# WiFiDMX4Channel.net
KiCad netlist of a schematic drawn in EAGLE
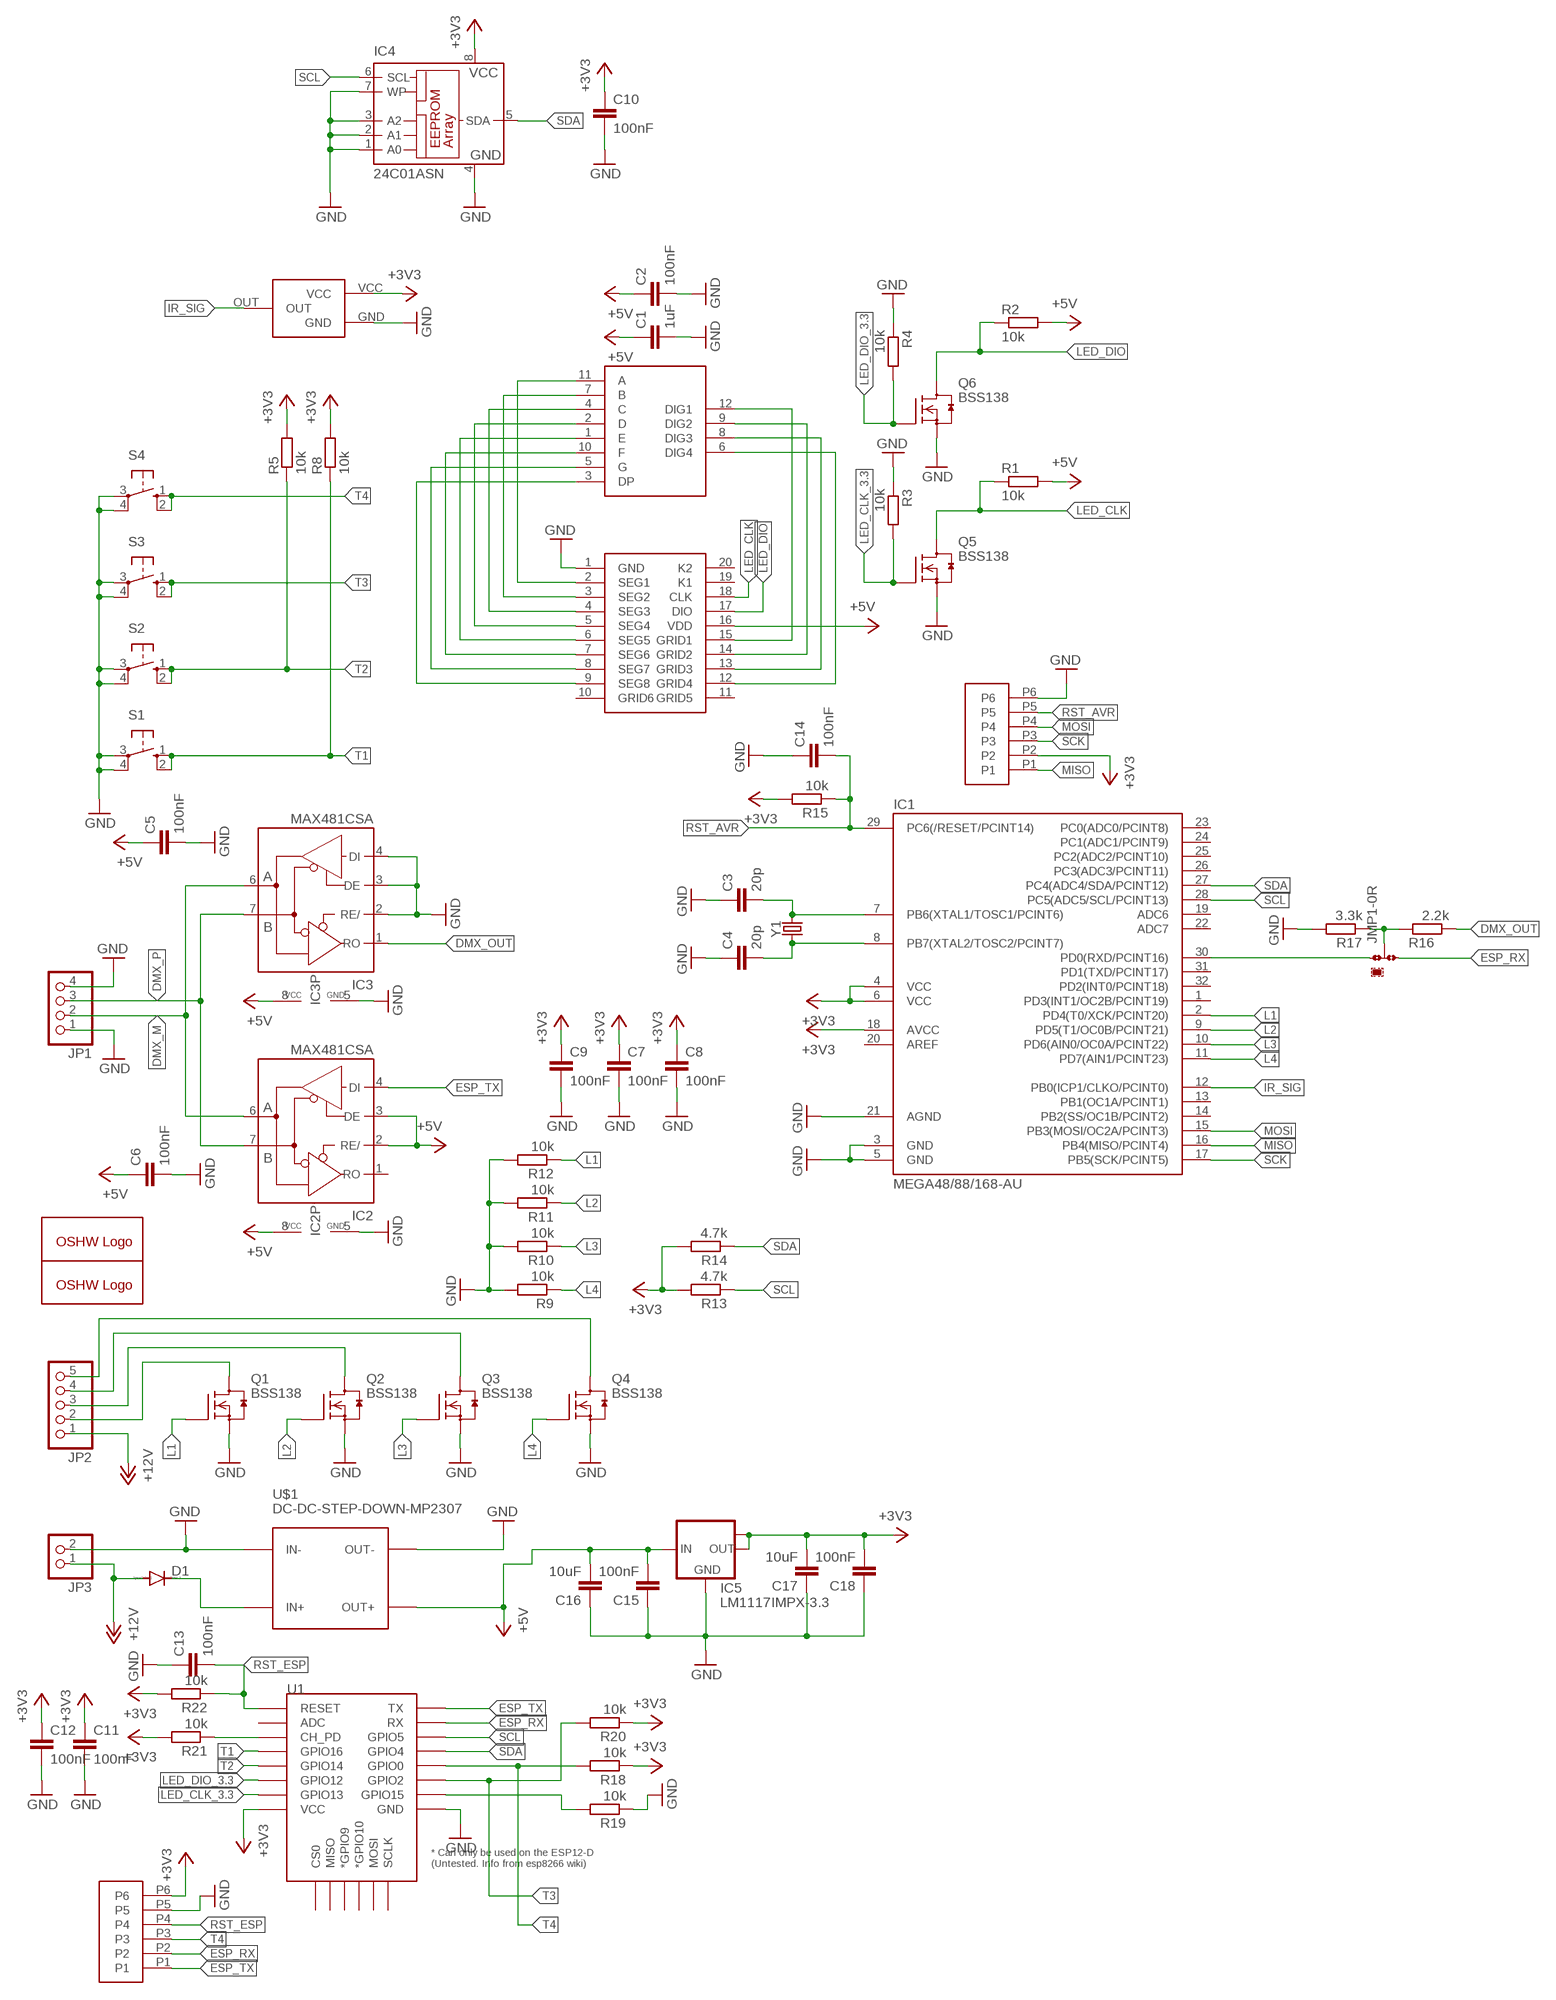
[diagram p0: schematic, sheet 1]

(export (version "E")
  (design (tool "Eeschema 10.0.6"))
  (components
    (comp (ref "C1")
      (value "1uF")
      (footprint "eagle-import:C0603")
      (libsource (lib "eagle-import") (part "C-EUC0603"))
    )
    (comp (ref "C2")
      (value "100nF")
      (footprint "eagle-import:C0603")
      (libsource (lib "eagle-import") (part "C-EUC0603"))
    )
    (comp (ref "C3")
      (value "20p")
      (footprint "eagle-import:C0603")
      (libsource (lib "eagle-import") (part "C-EUC0603"))
    )
    (comp (ref "C4")
      (value "20p")
      (footprint "eagle-import:C0603")
      (libsource (lib "eagle-import") (part "C-EUC0603"))
    )
    (comp (ref "C5")
      (value "100nF")
      (footprint "eagle-import:C0603")
      (libsource (lib "eagle-import") (part "C-EUC0603"))
    )
    (comp (ref "C6")
      (value "100nF")
      (footprint "eagle-import:C0603")
      (libsource (lib "eagle-import") (part "C-EUC0603"))
    )
    (comp (ref "C7")
      (value "100nF")
      (footprint "eagle-import:C0603")
      (libsource (lib "eagle-import") (part "C-EUC0603"))
    )
    (comp (ref "C8")
      (value "100nF")
      (footprint "eagle-import:C0603")
      (libsource (lib "eagle-import") (part "C-EUC0603"))
    )
    (comp (ref "C9")
      (value "100nF")
      (footprint "eagle-import:C0603")
      (libsource (lib "eagle-import") (part "C-EUC0603"))
    )
    (comp (ref "C10")
      (value "100nF")
      (footprint "eagle-import:C0603")
      (libsource (lib "eagle-import") (part "C-EUC0603"))
    )
    (comp (ref "C11")
      (value "100nF")
      (footprint "eagle-import:C0603")
      (libsource (lib "eagle-import") (part "C-EUC0603"))
    )
    (comp (ref "C12")
      (value "100nF")
      (footprint "eagle-import:C0603")
      (libsource (lib "eagle-import") (part "C-EUC0603"))
    )
    (comp (ref "C13")
      (value "100nF")
      (footprint "eagle-import:C0603")
      (libsource (lib "eagle-import") (part "C-EUC0603"))
    )
    (comp (ref "C14")
      (value "100nF")
      (footprint "eagle-import:C0603")
      (libsource (lib "eagle-import") (part "C-EUC0603"))
    )
    (comp (ref "C15")
      (value "100nF")
      (footprint "eagle-import:C0603")
      (libsource (lib "eagle-import") (part "C-EUC0603"))
    )
    (comp (ref "C16")
      (value "10uF")
      (footprint "eagle-import:C0603")
      (libsource (lib "eagle-import") (part "C-EUC0603"))
    )
    (comp (ref "C17")
      (value "10uF")
      (footprint "eagle-import:C0603")
      (libsource (lib "eagle-import") (part "C-EUC0603"))
    )
    (comp (ref "C18")
      (value "100nF")
      (footprint "eagle-import:C0603")
      (libsource (lib "eagle-import") (part "C-EUC0603"))
    )
    (comp (ref "D1")
      (value "DIODE-DO214AC")
      (footprint "eagle-import:DO214AC")
      (libsource (lib "eagle-import") (part "DIODE-DO214AC"))
    )
    (comp (ref "GOLD_ORB_SM1")
      (value "OSHWLOGOLOGO5MM")
      (footprint "eagle-import:OSHW_5MM")
      (libsource (lib "eagle-import") (part "OSHWLOGOLOGO5MM"))
    )
    (comp (ref "GOLD_ORB_SM2")
      (value "OSHWLOGOLOGO5MM")
      (footprint "eagle-import:OSHW_5MM")
      (libsource (lib "eagle-import") (part "OSHWLOGOLOGO5MM"))
    )
    (comp (ref "IC1")
      (value "MEGA48/88/168-AU")
      (footprint "eagle-import:TQFP32-08")
      (libsource (lib "eagle-import") (part "MEGA48/88/168-AU"))
    )
    (comp (ref "IC2")
      (value "MAX481CSA")
      (footprint "eagle-import:SO08")
      (libsource (lib "eagle-import") (part "MAX481CSA"))
    )
    (comp (ref "IC3")
      (value "MAX481CSA")
      (footprint "eagle-import:SO08")
      (libsource (lib "eagle-import") (part "MAX481CSA"))
    )
    (comp (ref "IC4")
      (value "24C01ASN")
      (footprint "eagle-import:SO-08")
      (fields (field (name "MPN") "AT24C01BN-SH-B"))
      (libsource (lib "eagle-import") (part "24CSN01A"))
    )
    (comp (ref "IC5")
      (value "LM1117IMPX-3.3")
      (footprint "eagle-import:SOT223")
      (libsource (lib "eagle-import") (part "LM1117IMPX-3.3"))
    )
    (comp (ref "JMP1")
      (value "0R-JUMPA")
      (footprint "eagle-import:A0R-JMP")
      (libsource (lib "eagle-import") (part "0R-JUMPA"))
    )
    (comp (ref "JP1")
      (value "PINHD-1X4_2.54")
      (footprint "eagle-import:1X04")
      (libsource (lib "eagle-import") (part "PINHD-1X4_2.54"))
    )
    (comp (ref "JP2")
      (value "PINHD-1X5_2.54")
      (footprint "eagle-import:1X05")
      (libsource (lib "eagle-import") (part "PINHD-1X5_2.54"))
    )
    (comp (ref "JP3")
      (value "PINHD-1X2_2.54")
      (footprint "eagle-import:1X02")
      (libsource (lib "eagle-import") (part "PINHD-1X2_2.54"))
    )
    (comp (ref "Q1")
      (value "BSS138")
      (footprint "eagle-import:SOT23")
      (libsource (lib "eagle-import") (part "BSS138"))
    )
    (comp (ref "Q2")
      (value "BSS138")
      (footprint "eagle-import:SOT23")
      (libsource (lib "eagle-import") (part "BSS138"))
    )
    (comp (ref "Q3")
      (value "BSS138")
      (footprint "eagle-import:SOT23")
      (libsource (lib "eagle-import") (part "BSS138"))
    )
    (comp (ref "Q4")
      (value "BSS138")
      (footprint "eagle-import:SOT23")
      (libsource (lib "eagle-import") (part "BSS138"))
    )
    (comp (ref "Q5")
      (value "BSS138")
      (footprint "eagle-import:SOT23")
      (libsource (lib "eagle-import") (part "BSS138"))
    )
    (comp (ref "Q6")
      (value "BSS138")
      (footprint "eagle-import:SOT23")
      (libsource (lib "eagle-import") (part "BSS138"))
    )
    (comp (ref "R1")
      (value "10k")
      (footprint "eagle-import:R0603")
      (libsource (lib "eagle-import") (part "R-EU_R0603"))
    )
    (comp (ref "R2")
      (value "10k")
      (footprint "eagle-import:R0603")
      (libsource (lib "eagle-import") (part "R-EU_R0603"))
    )
    (comp (ref "R3")
      (value "10k")
      (footprint "eagle-import:R0603")
      (libsource (lib "eagle-import") (part "R-EU_R0603"))
    )
    (comp (ref "R4")
      (value "10k")
      (footprint "eagle-import:R0603")
      (libsource (lib "eagle-import") (part "R-EU_R0603"))
    )
    (comp (ref "R5")
      (value "10k")
      (footprint "eagle-import:R0603")
      (libsource (lib "eagle-import") (part "R-EU_R0603"))
    )
    (comp (ref "R8")
      (value "10k")
      (footprint "eagle-import:R0603")
      (libsource (lib "eagle-import") (part "R-EU_R0603"))
    )
    (comp (ref "R9")
      (value "10k")
      (footprint "eagle-import:R0603")
      (libsource (lib "eagle-import") (part "R-EU_R0603"))
    )
    (comp (ref "R10")
      (value "10k")
      (footprint "eagle-import:R0603")
      (libsource (lib "eagle-import") (part "R-EU_R0603"))
    )
    (comp (ref "R11")
      (value "10k")
      (footprint "eagle-import:R0603")
      (libsource (lib "eagle-import") (part "R-EU_R0603"))
    )
    (comp (ref "R12")
      (value "10k")
      (footprint "eagle-import:R0603")
      (libsource (lib "eagle-import") (part "R-EU_R0603"))
    )
    (comp (ref "R13")
      (value "4.7k")
      (footprint "eagle-import:R0603")
      (libsource (lib "eagle-import") (part "R-EU_R0603"))
    )
    (comp (ref "R14")
      (value "4.7k")
      (footprint "eagle-import:R0603")
      (libsource (lib "eagle-import") (part "R-EU_R0603"))
    )
    (comp (ref "R15")
      (value "10k")
      (footprint "eagle-import:R0603")
      (libsource (lib "eagle-import") (part "R-EU_R0603"))
    )
    (comp (ref "R16")
      (value "2.2k")
      (footprint "eagle-import:R0603")
      (libsource (lib "eagle-import") (part "R-EU_R0603"))
    )
    (comp (ref "R17")
      (value "3.3k")
      (footprint "eagle-import:R0603")
      (libsource (lib "eagle-import") (part "R-EU_R0603"))
    )
    (comp (ref "R18")
      (value "10k")
      (footprint "eagle-import:R0603")
      (libsource (lib "eagle-import") (part "R-EU_R0603"))
    )
    (comp (ref "R19")
      (value "10k")
      (footprint "eagle-import:R0603")
      (libsource (lib "eagle-import") (part "R-EU_R0603"))
    )
    (comp (ref "R20")
      (value "10k")
      (footprint "eagle-import:R0603")
      (libsource (lib "eagle-import") (part "R-EU_R0603"))
    )
    (comp (ref "R21")
      (value "10k")
      (footprint "eagle-import:R0603")
      (libsource (lib "eagle-import") (part "R-EU_R0603"))
    )
    (comp (ref "R22")
      (value "10k")
      (footprint "eagle-import:R0603")
      (libsource (lib "eagle-import") (part "R-EU_R0603"))
    )
    (comp (ref "S1")
      (value "10-XX")
      (footprint "eagle-import:B3F-10XX")
      (fields (field (name "MPN") "B3F-1000"))
      (libsource (lib "eagle-import") (part "10-XX"))
    )
    (comp (ref "S2")
      (value "10-XX")
      (footprint "eagle-import:B3F-10XX")
      (fields (field (name "MPN") "B3F-1000"))
      (libsource (lib "eagle-import") (part "10-XX"))
    )
    (comp (ref "S3")
      (value "10-XX")
      (footprint "eagle-import:B3F-10XX")
      (fields (field (name "MPN") "B3F-1000"))
      (libsource (lib "eagle-import") (part "10-XX"))
    )
    (comp (ref "S4")
      (value "10-XX")
      (footprint "eagle-import:B3F-10XX")
      (fields (field (name "MPN") "B3F-1000"))
      (libsource (lib "eagle-import") (part "10-XX"))
    )
    (comp (ref "U$1")
      (value "DC-DC-STEP-DOWN-MP2307")
      (footprint "eagle-import:DC-DC-STEP-DOWN-MP2307")
      (libsource (lib "eagle-import") (part "DC-DC-STEP-DOWN-MP2307"))
    )
    (comp (ref "U$2")
      (value "4-DIGIT-7-SEGMENT")
      (footprint "eagle-import:7SETG-1")
      (libsource (lib "eagle-import") (part "4-DIGIT-7-SEGMENT"))
    )
    (comp (ref "U$3")
      (value "TM1637-SOP20")
      (footprint "eagle-import:SO20W")
      (libsource (lib "eagle-import") (part "TM1637-SOP20"))
    )
    (comp (ref "U$4")
      (value "PC838")
      (footprint "eagle-import:PC838")
      (libsource (lib "eagle-import") (part "PC838"))
    )
    (comp (ref "U$5")
      (value "6P-1.27")
      (footprint "eagle-import:6P-1.27")
      (libsource (lib "eagle-import") (part "6P-1.27"))
    )
    (comp (ref "U$6")
      (value "6P-1.27")
      (footprint "eagle-import:6P-1.27")
      (libsource (lib "eagle-import") (part "6P-1.27"))
    )
    (comp (ref "U1")
      (value "ESP12ESMD")
      (footprint "eagle-import:ESP12E-SMD")
      (libsource (lib "eagle-import") (part "ESP12ESMD"))
    )
    (comp (ref "Y1")
      (value "CRYSTALSMD-5X3.2-2PAD")
      (footprint "eagle-import:CRYSTAL-SMD-5X3.2-2PAD")
      (libsource (lib "eagle-import") (part "CRYSTALSMD-5X3.2-2PAD"))
    )
  )
  (nets
    (net (code "1") (name "+3V3") (class "Default")
      (node (ref "C10") (pin "1") (pinfunction "1_1") (pintype "passive"))
      (node (ref "C11") (pin "1") (pinfunction "1_1") (pintype "passive"))
      (node (ref "C12") (pin "1") (pinfunction "1_1") (pintype "passive"))
      (node (ref "C17") (pin "2") (pinfunction "2_2") (pintype "passive"))
      (node (ref "C18") (pin "2") (pinfunction "2_2") (pintype "passive"))
      (node (ref "C7") (pin "1") (pinfunction "1_1") (pintype "passive"))
      (node (ref "C8") (pin "1") (pinfunction "1_1") (pintype "passive"))
      (node (ref "C9") (pin "1") (pinfunction "1_1") (pintype "passive"))
      (node (ref "IC1") (pin "18") (pinfunction "AVCC_18") (pintype "passive"))
      (node (ref "IC1") (pin "4") (pinfunction "VCC_4") (pintype "power_in"))
      (node (ref "IC1") (pin "6") (pinfunction "VCC_6") (pintype "power_in"))
      (node (ref "IC4") (pin "8") (pinfunction "VCC_8") (pintype "power_in"))
      (node (ref "IC5") (pin "2") (pinfunction "OUT_2") (pintype "passive"))
      (node (ref "IC5") (pin "TAB") (pinfunction "OUT1_TAB") (pintype "passive"))
      (node (ref "R13") (pin "2") (pinfunction "2_2") (pintype "passive"))
      (node (ref "R14") (pin "2") (pinfunction "2_2") (pintype "passive"))
      (node (ref "R15") (pin "2") (pinfunction "2_2") (pintype "passive"))
      (node (ref "R18") (pin "1") (pinfunction "1_1") (pintype "passive"))
      (node (ref "R20") (pin "1") (pinfunction "1_1") (pintype "passive"))
      (node (ref "R21") (pin "2") (pinfunction "2_2") (pintype "passive"))
      (node (ref "R22") (pin "2") (pinfunction "2_2") (pintype "passive"))
      (node (ref "R5") (pin "2") (pinfunction "2_2") (pintype "passive"))
      (node (ref "R8") (pin "2") (pinfunction "2_2") (pintype "passive"))
      (node (ref "U$4") (pin "VCC") (pinfunction "VCC_VCC") (pintype "bidirectional"))
      (node (ref "U$5") (pin "P6") (pinfunction "P6_P6") (pintype "bidirectional"))
      (node (ref "U$6") (pin "P2") (pinfunction "P2_P2") (pintype "bidirectional"))
      (node (ref "U1") (pin "VCC") (pinfunction "VCC_VCC") (pintype "bidirectional"))
    )
    (net (code "2") (name "+5V") (class "Default")
      (node (ref "C1") (pin "1") (pinfunction "1_1") (pintype "passive"))
      (node (ref "C15") (pin "2") (pinfunction "2_2") (pintype "passive"))
      (node (ref "C16") (pin "2") (pinfunction "2_2") (pintype "passive"))
      (node (ref "C2") (pin "1") (pinfunction "1_1") (pintype "passive"))
      (node (ref "C5") (pin "1") (pinfunction "1_1") (pintype "passive"))
      (node (ref "C6") (pin "1") (pinfunction "1_1") (pintype "passive"))
      (node (ref "IC2") (pin "2") (pinfunction "RE/_2") (pintype "input"))
      (node (ref "IC2") (pin "3") (pinfunction "DE_3") (pintype "input"))
      (node (ref "IC2") (pin "8") (pinfunction "VCC_8") (pintype "power_in"))
      (node (ref "IC3") (pin "8") (pinfunction "VCC_8") (pintype "power_in"))
      (node (ref "IC5") (pin "3") (pinfunction "IN_3") (pintype "input"))
      (node (ref "R1") (pin "2") (pinfunction "2_2") (pintype "passive"))
      (node (ref "R2") (pin "2") (pinfunction "2_2") (pintype "passive"))
      (node (ref "U$1") (pin "OUT+") (pinfunction "OUT+_OUT+") (pintype "bidirectional"))
      (node (ref "U$3") (pin "16") (pinfunction "VDD_16") (pintype "bidirectional"))
    )
    (net (code "3") (name "+12V") (class "Default")
      (node (ref "D1") (pin "A") (pinfunction "A_A") (pintype "passive"))
      (node (ref "JP2") (pin "1") (pinfunction "1_1") (pintype "passive"))
      (node (ref "JP3") (pin "1") (pinfunction "1_1") (pintype "passive"))
    )
    (net (code "4") (name "DMX_M") (class "Default")
      (node (ref "IC2") (pin "6") (pinfunction "A_6") (pintype "passive"))
      (node (ref "IC3") (pin "6") (pinfunction "A_6") (pintype "passive"))
      (node (ref "JP1") (pin "2") (pinfunction "2_2") (pintype "passive"))
    )
    (net (code "5") (name "DMX_OUT") (class "Default")
      (node (ref "IC3") (pin "1") (pinfunction "RO_1") (pintype "output"))
      (node (ref "R16") (pin "1") (pinfunction "1_1") (pintype "passive"))
    )
    (net (code "6") (name "DMX_P") (class "Default")
      (node (ref "IC2") (pin "7") (pinfunction "B_7") (pintype "passive"))
      (node (ref "IC3") (pin "7") (pinfunction "B_7") (pintype "passive"))
      (node (ref "JP1") (pin "3") (pinfunction "3_3") (pintype "passive"))
    )
    (net (code "7") (name "ESP_RX") (class "Default")
      (node (ref "JMP1") (pin "3") (pinfunction "3_3") (pintype "passive"))
      (node (ref "U$5") (pin "P2") (pinfunction "P2_P2") (pintype "bidirectional"))
      (node (ref "U1") (pin "RXD0") (pinfunction "RX_RXD0") (pintype "bidirectional"))
    )
    (net (code "8") (name "ESP_TX") (class "Default")
      (node (ref "IC2") (pin "4") (pinfunction "DI_4") (pintype "input"))
      (node (ref "U$5") (pin "P1") (pinfunction "P1_P1") (pintype "bidirectional"))
      (node (ref "U1") (pin "TXD0") (pinfunction "TX_TXD0") (pintype "bidirectional"))
    )
    (net (code "9") (name "GND") (class "Default")
      (node (ref "C1") (pin "2") (pinfunction "2_2") (pintype "passive"))
      (node (ref "C10") (pin "2") (pinfunction "2_2") (pintype "passive"))
      (node (ref "C11") (pin "2") (pinfunction "2_2") (pintype "passive"))
      (node (ref "C12") (pin "2") (pinfunction "2_2") (pintype "passive"))
      (node (ref "C13") (pin "1") (pinfunction "1_1") (pintype "passive"))
      (node (ref "C14") (pin "1") (pinfunction "1_1") (pintype "passive"))
      (node (ref "C15") (pin "1") (pinfunction "1_1") (pintype "passive"))
      (node (ref "C16") (pin "1") (pinfunction "1_1") (pintype "passive"))
      (node (ref "C17") (pin "1") (pinfunction "1_1") (pintype "passive"))
      (node (ref "C18") (pin "1") (pinfunction "1_1") (pintype "passive"))
      (node (ref "C2") (pin "2") (pinfunction "2_2") (pintype "passive"))
      (node (ref "C3") (pin "1") (pinfunction "1_1") (pintype "passive"))
      (node (ref "C4") (pin "1") (pinfunction "1_1") (pintype "passive"))
      (node (ref "C5") (pin "2") (pinfunction "2_2") (pintype "passive"))
      (node (ref "C6") (pin "2") (pinfunction "2_2") (pintype "passive"))
      (node (ref "C7") (pin "2") (pinfunction "2_2") (pintype "passive"))
      (node (ref "C8") (pin "2") (pinfunction "2_2") (pintype "passive"))
      (node (ref "C9") (pin "2") (pinfunction "2_2") (pintype "passive"))
      (node (ref "IC1") (pin "21") (pinfunction "AGND_21") (pintype "power_in"))
      (node (ref "IC1") (pin "3") (pinfunction "GND_3") (pintype "power_in"))
      (node (ref "IC1") (pin "5") (pinfunction "GND_5") (pintype "power_in"))
      (node (ref "IC2") (pin "5") (pinfunction "GND_5") (pintype "power_in"))
      (node (ref "IC3") (pin "2") (pinfunction "RE/_2") (pintype "input"))
      (node (ref "IC3") (pin "3") (pinfunction "DE_3") (pintype "input"))
      (node (ref "IC3") (pin "4") (pinfunction "DI_4") (pintype "input"))
      (node (ref "IC3") (pin "5") (pinfunction "GND_5") (pintype "power_in"))
      (node (ref "IC4") (pin "1") (pinfunction "A0_1") (pintype "input"))
      (node (ref "IC4") (pin "2") (pinfunction "A1_2") (pintype "input"))
      (node (ref "IC4") (pin "3") (pinfunction "A2_3") (pintype "input"))
      (node (ref "IC4") (pin "4") (pinfunction "GND_4") (pintype "power_in"))
      (node (ref "IC4") (pin "7") (pinfunction "WP_7") (pintype "input"))
      (node (ref "IC5") (pin "1") (pinfunction "GND_1") (pintype "input"))
      (node (ref "JP1") (pin "1") (pinfunction "1_1") (pintype "passive"))
      (node (ref "JP1") (pin "4") (pinfunction "4_4") (pintype "passive"))
      (node (ref "JP3") (pin "2") (pinfunction "2_2") (pintype "passive"))
      (node (ref "Q1") (pin "2") (pinfunction "S_2") (pintype "passive"))
      (node (ref "Q2") (pin "2") (pinfunction "S_2") (pintype "passive"))
      (node (ref "Q3") (pin "2") (pinfunction "S_2") (pintype "passive"))
      (node (ref "Q4") (pin "2") (pinfunction "S_2") (pintype "passive"))
      (node (ref "Q5") (pin "2") (pinfunction "S_2") (pintype "passive"))
      (node (ref "Q6") (pin "2") (pinfunction "S_2") (pintype "passive"))
      (node (ref "R10") (pin "2") (pinfunction "2_2") (pintype "passive"))
      (node (ref "R11") (pin "2") (pinfunction "2_2") (pintype "passive"))
      (node (ref "R12") (pin "2") (pinfunction "2_2") (pintype "passive"))
      (node (ref "R17") (pin "2") (pinfunction "2_2") (pintype "passive"))
      (node (ref "R19") (pin "1") (pinfunction "1_1") (pintype "passive"))
      (node (ref "R3") (pin "1") (pinfunction "1_1") (pintype "passive"))
      (node (ref "R4") (pin "1") (pinfunction "1_1") (pintype "passive"))
      (node (ref "R9") (pin "2") (pinfunction "2_2") (pintype "passive"))
      (node (ref "S1") (pin "3") (pinfunction "P_3") (pintype "passive"))
      (node (ref "S1") (pin "4") (pinfunction "P1_4") (pintype "passive"))
      (node (ref "S2") (pin "3") (pinfunction "P_3") (pintype "passive"))
      (node (ref "S2") (pin "4") (pinfunction "P1_4") (pintype "passive"))
      (node (ref "S3") (pin "3") (pinfunction "P_3") (pintype "passive"))
      (node (ref "S3") (pin "4") (pinfunction "P1_4") (pintype "passive"))
      (node (ref "S4") (pin "3") (pinfunction "P_3") (pintype "passive"))
      (node (ref "S4") (pin "4") (pinfunction "P1_4") (pintype "passive"))
      (node (ref "U$1") (pin "IN-") (pinfunction "IN-_IN-") (pintype "bidirectional"))
      (node (ref "U$1") (pin "OUT-") (pinfunction "OUT-_OUT-") (pintype "bidirectional"))
      (node (ref "U$3") (pin "1") (pinfunction "GND_1") (pintype "bidirectional"))
      (node (ref "U$4") (pin "GND") (pinfunction "GND_GND") (pintype "bidirectional"))
      (node (ref "U$5") (pin "P5") (pinfunction "P5_P5") (pintype "bidirectional"))
      (node (ref "U$6") (pin "P6") (pinfunction "P6_P6") (pintype "bidirectional"))
      (node (ref "U1") (pin "GND") (pinfunction "GND_GND") (pintype "bidirectional"))
    )
    (net (code "10") (name "IR_SIG") (class "Default")
      (node (ref "IC1") (pin "12") (pinfunction "PB0(ICP1/CLKO/PCINT0)_12") (pintype "bidirectional"))
      (node (ref "U$4") (pin "OUT") (pinfunction "OUT_OUT") (pintype "bidirectional"))
    )
    (net (code "11") (name "L1") (class "Default")
      (node (ref "IC1") (pin "2") (pinfunction "PD4(T0/XCK/PCINT20)_2") (pintype "bidirectional"))
      (node (ref "Q1") (pin "1") (pinfunction "G_1") (pintype "passive"))
      (node (ref "R12") (pin "1") (pinfunction "1_1") (pintype "passive"))
    )
    (net (code "12") (name "L2") (class "Default")
      (node (ref "IC1") (pin "9") (pinfunction "PD5(T1/OC0B/PCINT21)_9") (pintype "bidirectional"))
      (node (ref "Q2") (pin "1") (pinfunction "G_1") (pintype "passive"))
      (node (ref "R11") (pin "1") (pinfunction "1_1") (pintype "passive"))
    )
    (net (code "13") (name "L3") (class "Default")
      (node (ref "IC1") (pin "10") (pinfunction "PD6(AIN0/OC0A/PCINT22)_10") (pintype "bidirectional"))
      (node (ref "Q3") (pin "1") (pinfunction "G_1") (pintype "passive"))
      (node (ref "R10") (pin "1") (pinfunction "1_1") (pintype "passive"))
    )
    (net (code "14") (name "L4") (class "Default")
      (node (ref "IC1") (pin "11") (pinfunction "PD7(AIN1/PCINT23)_11") (pintype "bidirectional"))
      (node (ref "Q4") (pin "1") (pinfunction "G_1") (pintype "passive"))
      (node (ref "R9") (pin "1") (pinfunction "1_1") (pintype "passive"))
    )
    (net (code "15") (name "LED_CLK") (class "Default")
      (node (ref "Q5") (pin "3") (pinfunction "D_3") (pintype "passive"))
      (node (ref "R1") (pin "1") (pinfunction "1_1") (pintype "passive"))
      (node (ref "U$3") (pin "18") (pinfunction "CLK_18") (pintype "bidirectional"))
    )
    (net (code "16") (name "LED_CLK_3.3") (class "Default")
      (node (ref "Q5") (pin "1") (pinfunction "G_1") (pintype "passive"))
      (node (ref "R3") (pin "2") (pinfunction "2_2") (pintype "passive"))
      (node (ref "U1") (pin "GPIO13") (pinfunction "GPIO13_GPIO13") (pintype "bidirectional"))
    )
    (net (code "17") (name "LED_DIO") (class "Default")
      (node (ref "Q6") (pin "3") (pinfunction "D_3") (pintype "passive"))
      (node (ref "R2") (pin "1") (pinfunction "1_1") (pintype "passive"))
      (node (ref "U$3") (pin "17") (pinfunction "DIO_17") (pintype "bidirectional"))
    )
    (net (code "18") (name "LED_DIO_3.3") (class "Default")
      (node (ref "Q6") (pin "1") (pinfunction "G_1") (pintype "passive"))
      (node (ref "R4") (pin "2") (pinfunction "2_2") (pintype "passive"))
      (node (ref "U1") (pin "GPIO12") (pinfunction "GPIO12_GPIO12") (pintype "bidirectional"))
    )
    (net (code "19") (name "MISO") (class "Default")
      (node (ref "IC1") (pin "16") (pinfunction "PB4(MISO/PCINT4)_16") (pintype "bidirectional"))
      (node (ref "U$6") (pin "P1") (pinfunction "P1_P1") (pintype "bidirectional"))
    )
    (net (code "20") (name "MOSI") (class "Default")
      (node (ref "IC1") (pin "15") (pinfunction "PB3(MOSI/OC2A/PCINT3)_15") (pintype "bidirectional"))
      (node (ref "U$6") (pin "P4") (pinfunction "P4_P4") (pintype "bidirectional"))
    )
    (net (code "21") (name "Net-(D1-PadC)") (class "Default")
      (node (ref "D1") (pin "C") (pinfunction "C_C") (pintype "passive"))
      (node (ref "U$1") (pin "IN+") (pinfunction "IN+_IN+") (pintype "bidirectional"))
    )
    (net (code "22") (name "Net-(IC1-PB6(XTAL1{slash}TOSC1{slash}PCINT6))") (class "Default")
      (node (ref "C3") (pin "2") (pinfunction "2_2") (pintype "passive"))
      (node (ref "IC1") (pin "7") (pinfunction "PB6(XTAL1/TOSC1/PCINT6)_7") (pintype "bidirectional"))
      (node (ref "Y1") (pin "P$2") (pinfunction "2_P$2") (pintype "passive"))
    )
    (net (code "23") (name "Net-(IC1-PB7(XTAL2{slash}TOSC2{slash}PCINT7))") (class "Default")
      (node (ref "C4") (pin "2") (pinfunction "2_2") (pintype "passive"))
      (node (ref "IC1") (pin "8") (pinfunction "PB7(XTAL2/TOSC2/PCINT7)_8") (pintype "bidirectional"))
      (node (ref "Y1") (pin "P$1") (pinfunction "1_P$1") (pintype "passive"))
    )
    (net (code "24") (name "Net-(IC1-PD0(RXD{slash}PCINT16))") (class "Default")
      (node (ref "IC1") (pin "30") (pinfunction "PD0(RXD/PCINT16)_30") (pintype "bidirectional"))
      (node (ref "JMP1") (pin "1") (pinfunction "1_1") (pintype "passive"))
    )
    (net (code "25") (name "Net-(JMP1-Pad2)") (class "Default")
      (node (ref "JMP1") (pin "2") (pinfunction "2_2") (pintype "passive"))
      (node (ref "R16") (pin "2") (pinfunction "2_2") (pintype "passive"))
      (node (ref "R17") (pin "1") (pinfunction "1_1") (pintype "passive"))
    )
    (net (code "26") (name "Net-(Q1-D)") (class "Default")
      (node (ref "JP2") (pin "2") (pinfunction "2_2") (pintype "passive"))
      (node (ref "Q1") (pin "3") (pinfunction "D_3") (pintype "passive"))
    )
    (net (code "27") (name "Net-(Q2-D)") (class "Default")
      (node (ref "JP2") (pin "3") (pinfunction "3_3") (pintype "passive"))
      (node (ref "Q2") (pin "3") (pinfunction "D_3") (pintype "passive"))
    )
    (net (code "28") (name "Net-(Q3-D)") (class "Default")
      (node (ref "JP2") (pin "4") (pinfunction "4_4") (pintype "passive"))
      (node (ref "Q3") (pin "3") (pinfunction "D_3") (pintype "passive"))
    )
    (net (code "29") (name "Net-(Q4-D)") (class "Default")
      (node (ref "JP2") (pin "5") (pinfunction "5_5") (pintype "passive"))
      (node (ref "Q4") (pin "3") (pinfunction "D_3") (pintype "passive"))
    )
    (net (code "30") (name "Net-(R19-Pad2)") (class "Default")
      (node (ref "R19") (pin "2") (pinfunction "2_2") (pintype "passive"))
      (node (ref "U1") (pin "GPIO15") (pinfunction "GPIO15_GPIO15") (pintype "bidirectional"))
    )
    (net (code "31") (name "Net-(R21-Pad1)") (class "Default")
      (node (ref "R21") (pin "1") (pinfunction "1_1") (pintype "passive"))
      (node (ref "U1") (pin "CH_PD") (pinfunction "CH_PD_CH_PD") (pintype "bidirectional"))
    )
    (net (code "32") (name "Net-(U$2-A)") (class "Default")
      (node (ref "U$2") (pin "11") (pinfunction "A_11") (pintype "bidirectional"))
      (node (ref "U$3") (pin "2") (pinfunction "SEG1_2") (pintype "bidirectional"))
    )
    (net (code "33") (name "Net-(U$2-B)") (class "Default")
      (node (ref "U$2") (pin "7") (pinfunction "B_7") (pintype "bidirectional"))
      (node (ref "U$3") (pin "3") (pinfunction "SEG2_3") (pintype "bidirectional"))
    )
    (net (code "34") (name "Net-(U$2-C)") (class "Default")
      (node (ref "U$2") (pin "4") (pinfunction "C_4") (pintype "bidirectional"))
      (node (ref "U$3") (pin "4") (pinfunction "SEG3_4") (pintype "bidirectional"))
    )
    (net (code "35") (name "Net-(U$2-D)") (class "Default")
      (node (ref "U$2") (pin "2") (pinfunction "D_2") (pintype "bidirectional"))
      (node (ref "U$3") (pin "5") (pinfunction "SEG4_5") (pintype "bidirectional"))
    )
    (net (code "36") (name "Net-(U$2-DIG1)") (class "Default")
      (node (ref "U$2") (pin "12") (pinfunction "DIG1_12") (pintype "bidirectional"))
      (node (ref "U$3") (pin "15") (pinfunction "GRID1_15") (pintype "bidirectional"))
    )
    (net (code "37") (name "Net-(U$2-DIG2)") (class "Default")
      (node (ref "U$2") (pin "9") (pinfunction "DIG2_9") (pintype "bidirectional"))
      (node (ref "U$3") (pin "14") (pinfunction "GRID2_14") (pintype "bidirectional"))
    )
    (net (code "38") (name "Net-(U$2-DIG3)") (class "Default")
      (node (ref "U$2") (pin "8") (pinfunction "DIG3_8") (pintype "bidirectional"))
      (node (ref "U$3") (pin "13") (pinfunction "GRID3_13") (pintype "bidirectional"))
    )
    (net (code "39") (name "Net-(U$2-DIG4)") (class "Default")
      (node (ref "U$2") (pin "6") (pinfunction "DIG4_6") (pintype "bidirectional"))
      (node (ref "U$3") (pin "12") (pinfunction "GRID4_12") (pintype "bidirectional"))
    )
    (net (code "40") (name "Net-(U$2-DP)") (class "Default")
      (node (ref "U$2") (pin "3") (pinfunction "DP_3") (pintype "bidirectional"))
      (node (ref "U$3") (pin "9") (pinfunction "SEG8_9") (pintype "bidirectional"))
    )
    (net (code "41") (name "Net-(U$2-E)") (class "Default")
      (node (ref "U$2") (pin "1") (pinfunction "E_1") (pintype "bidirectional"))
      (node (ref "U$3") (pin "6") (pinfunction "SEG5_6") (pintype "bidirectional"))
    )
    (net (code "42") (name "Net-(U$2-F)") (class "Default")
      (node (ref "U$2") (pin "10") (pinfunction "F_10") (pintype "bidirectional"))
      (node (ref "U$3") (pin "7") (pinfunction "SEG6_7") (pintype "bidirectional"))
    )
    (net (code "43") (name "Net-(U$2-G)") (class "Default")
      (node (ref "U$2") (pin "5") (pinfunction "G_5") (pintype "bidirectional"))
      (node (ref "U$3") (pin "8") (pinfunction "SEG7_8") (pintype "bidirectional"))
    )
    (net (code "44") (name "RST_AVR") (class "Default")
      (node (ref "C14") (pin "2") (pinfunction "2_2") (pintype "passive"))
      (node (ref "IC1") (pin "29") (pinfunction "PC6(/RESET/PCINT14)_29") (pintype "bidirectional"))
      (node (ref "R15") (pin "1") (pinfunction "1_1") (pintype "passive"))
      (node (ref "U$6") (pin "P5") (pinfunction "P5_P5") (pintype "bidirectional"))
    )
    (net (code "45") (name "RST_ESP") (class "Default")
      (node (ref "C13") (pin "2") (pinfunction "2_2") (pintype "passive"))
      (node (ref "R22") (pin "1") (pinfunction "1_1") (pintype "passive"))
      (node (ref "U$5") (pin "P4") (pinfunction "P4_P4") (pintype "bidirectional"))
      (node (ref "U1") (pin "RESET") (pinfunction "RESET_RESET") (pintype "bidirectional"))
    )
    (net (code "46") (name "SCK") (class "Default")
      (node (ref "IC1") (pin "17") (pinfunction "PB5(SCK/PCINT5)_17") (pintype "bidirectional"))
      (node (ref "U$6") (pin "P3") (pinfunction "P3_P3") (pintype "bidirectional"))
    )
    (net (code "47") (name "SCL") (class "Default")
      (node (ref "IC1") (pin "28") (pinfunction "PC5(ADC5/SCL/PCINT13)_28") (pintype "bidirectional"))
      (node (ref "IC4") (pin "6") (pinfunction "SCL_6") (pintype "input"))
      (node (ref "R13") (pin "1") (pinfunction "1_1") (pintype "passive"))
      (node (ref "U1") (pin "GPIO5") (pinfunction "GPIO5_GPIO5") (pintype "bidirectional"))
    )
    (net (code "48") (name "SDA") (class "Default")
      (node (ref "IC1") (pin "27") (pinfunction "PC4(ADC4/SDA/PCINT12)_27") (pintype "bidirectional"))
      (node (ref "IC4") (pin "5") (pinfunction "SDA_5") (pintype "bidirectional"))
      (node (ref "R14") (pin "1") (pinfunction "1_1") (pintype "passive"))
      (node (ref "U1") (pin "GPIO4") (pinfunction "GPIO4_GPIO4") (pintype "bidirectional"))
    )
    (net (code "49") (name "T1") (class "Default")
      (node (ref "R8") (pin "1") (pinfunction "1_1") (pintype "passive"))
      (node (ref "S1") (pin "1") (pinfunction "S_1") (pintype "passive"))
      (node (ref "S1") (pin "2") (pinfunction "S1_2") (pintype "passive"))
      (node (ref "U1") (pin "GPIO16") (pinfunction "GPIO16_GPIO16") (pintype "bidirectional"))
    )
    (net (code "50") (name "T2") (class "Default")
      (node (ref "R5") (pin "1") (pinfunction "1_1") (pintype "passive"))
      (node (ref "S2") (pin "1") (pinfunction "S_1") (pintype "passive"))
      (node (ref "S2") (pin "2") (pinfunction "S1_2") (pintype "passive"))
      (node (ref "U1") (pin "GPIO14") (pinfunction "GPIO14_GPIO14") (pintype "bidirectional"))
    )
    (net (code "51") (name "T3") (class "Default")
      (node (ref "R20") (pin "2") (pinfunction "2_2") (pintype "passive"))
      (node (ref "S3") (pin "1") (pinfunction "S_1") (pintype "passive"))
      (node (ref "S3") (pin "2") (pinfunction "S1_2") (pintype "passive"))
      (node (ref "U1") (pin "GPIO2") (pinfunction "GPIO2_GPIO2") (pintype "bidirectional"))
    )
    (net (code "52") (name "T4") (class "Default")
      (node (ref "R18") (pin "2") (pinfunction "2_2") (pintype "passive"))
      (node (ref "S4") (pin "1") (pinfunction "S_1") (pintype "passive"))
      (node (ref "S4") (pin "2") (pinfunction "S1_2") (pintype "passive"))
      (node (ref "U$5") (pin "P3") (pinfunction "P3_P3") (pintype "bidirectional"))
      (node (ref "U1") (pin "GPIO0") (pinfunction "GPIO0_GPIO0") (pintype "bidirectional"))
    )
    (net (code "53") (name "unconnected-(IC1-ADC6-Pad19)") (class "Default")
      (node (ref "IC1") (pin "19") (pinfunction "ADC6_19") (pintype "passive"))
    )
    (net (code "54") (name "unconnected-(IC1-ADC7-Pad22)") (class "Default")
      (node (ref "IC1") (pin "22") (pinfunction "ADC7_22") (pintype "passive"))
    )
    (net (code "55") (name "unconnected-(IC1-AREF-Pad20)") (class "Default")
      (node (ref "IC1") (pin "20") (pinfunction "AREF_20") (pintype "passive"))
    )
    (net (code "56") (name "unconnected-(IC1-PB1(OC1A{slash}PCINT1)-Pad13)") (class "Default")
      (node (ref "IC1") (pin "13") (pinfunction "PB1(OC1A/PCINT1)_13") (pintype "bidirectional"))
    )
    (net (code "57") (name "unconnected-(IC1-PB2(SS{slash}OC1B{slash}PCINT2)-Pad14)") (class "Default")
      (node (ref "IC1") (pin "14") (pinfunction "PB2(SS/OC1B/PCINT2)_14") (pintype "bidirectional"))
    )
    (net (code "58") (name "unconnected-(IC1-PC0(ADC0{slash}PCINT8)-Pad23)") (class "Default")
      (node (ref "IC1") (pin "23") (pinfunction "PC0(ADC0/PCINT8)_23") (pintype "bidirectional"))
    )
    (net (code "59") (name "unconnected-(IC1-PC1(ADC1{slash}PCINT9)-Pad24)") (class "Default")
      (node (ref "IC1") (pin "24") (pinfunction "PC1(ADC1/PCINT9)_24") (pintype "bidirectional"))
    )
    (net (code "60") (name "unconnected-(IC1-PC2(ADC2{slash}PCINT10)-Pad25)") (class "Default")
      (node (ref "IC1") (pin "25") (pinfunction "PC2(ADC2/PCINT10)_25") (pintype "bidirectional"))
    )
    (net (code "61") (name "unconnected-(IC1-PC3(ADC3{slash}PCINT11)-Pad26)") (class "Default")
      (node (ref "IC1") (pin "26") (pinfunction "PC3(ADC3/PCINT11)_26") (pintype "bidirectional"))
    )
    (net (code "62") (name "unconnected-(IC1-PD1(TXD{slash}PCINT17)-Pad31)") (class "Default")
      (node (ref "IC1") (pin "31") (pinfunction "PD1(TXD/PCINT17)_31") (pintype "bidirectional"))
    )
    (net (code "63") (name "unconnected-(IC1-PD2(INT0{slash}PCINT18)-Pad32)") (class "Default")
      (node (ref "IC1") (pin "32") (pinfunction "PD2(INT0/PCINT18)_32") (pintype "bidirectional"))
    )
    (net (code "64") (name "unconnected-(IC1-PD3(INT1{slash}OC2B{slash}PCINT19)-Pad1)") (class "Default")
      (node (ref "IC1") (pin "1") (pinfunction "PD3(INT1/OC2B/PCINT19)_1") (pintype "bidirectional"))
    )
    (net (code "65") (name "unconnected-(IC2A-RO-Pad1)") (class "Default")
      (node (ref "IC2") (pin "1") (pinfunction "RO_1") (pintype "output"))
    )
    (net (code "66") (name "unconnected-(U$3-GRID5-Pad11)") (class "Default")
      (node (ref "U$3") (pin "11") (pinfunction "GRID5_11") (pintype "bidirectional"))
    )
    (net (code "67") (name "unconnected-(U$3-GRID6-Pad10)") (class "Default")
      (node (ref "U$3") (pin "10") (pinfunction "GRID6_10") (pintype "bidirectional"))
    )
    (net (code "68") (name "unconnected-(U$3-K1-Pad19)") (class "Default")
      (node (ref "U$3") (pin "19") (pinfunction "K1_19") (pintype "bidirectional"))
    )
    (net (code "69") (name "unconnected-(U$3-K2-Pad20)") (class "Default")
      (node (ref "U$3") (pin "20") (pinfunction "K2_20") (pintype "bidirectional"))
    )
    (net (code "70") (name "unconnected-(U1-*GPIO9-PadGPIO9)") (class "Default")
      (node (ref "U1") (pin "GPIO9") (pinfunction "*GPIO9_GPIO9") (pintype "bidirectional"))
    )
    (net (code "71") (name "unconnected-(U1-*GPIO10-PadGPIO10)") (class "Default")
      (node (ref "U1") (pin "GPIO10") (pinfunction "*GPIO10_GPIO10") (pintype "bidirectional"))
    )
    (net (code "72") (name "unconnected-(U1-PadADC)") (class "Default")
      (node (ref "U1") (pin "ADC") (pinfunction "ADC_ADC") (pintype "bidirectional"))
    )
    (net (code "73") (name "unconnected-(U1-PadCS0)") (class "Default")
      (node (ref "U1") (pin "CS0") (pinfunction "CS0_CS0") (pintype "bidirectional"))
    )
    (net (code "74") (name "unconnected-(U1-PadMISO)") (class "Default")
      (node (ref "U1") (pin "MISO") (pinfunction "MISO_MISO") (pintype "bidirectional"))
    )
    (net (code "75") (name "unconnected-(U1-PadMOSI)") (class "Default")
      (node (ref "U1") (pin "MOSI") (pinfunction "MOSI_MOSI") (pintype "bidirectional"))
    )
    (net (code "76") (name "unconnected-(U1-PadSCLK)") (class "Default")
      (node (ref "U1") (pin "SCLK") (pinfunction "SCLK_SCLK") (pintype "bidirectional"))
    )
  )
)
